# design.net
KiCad netlist of a schematic drawn in Altium Designer
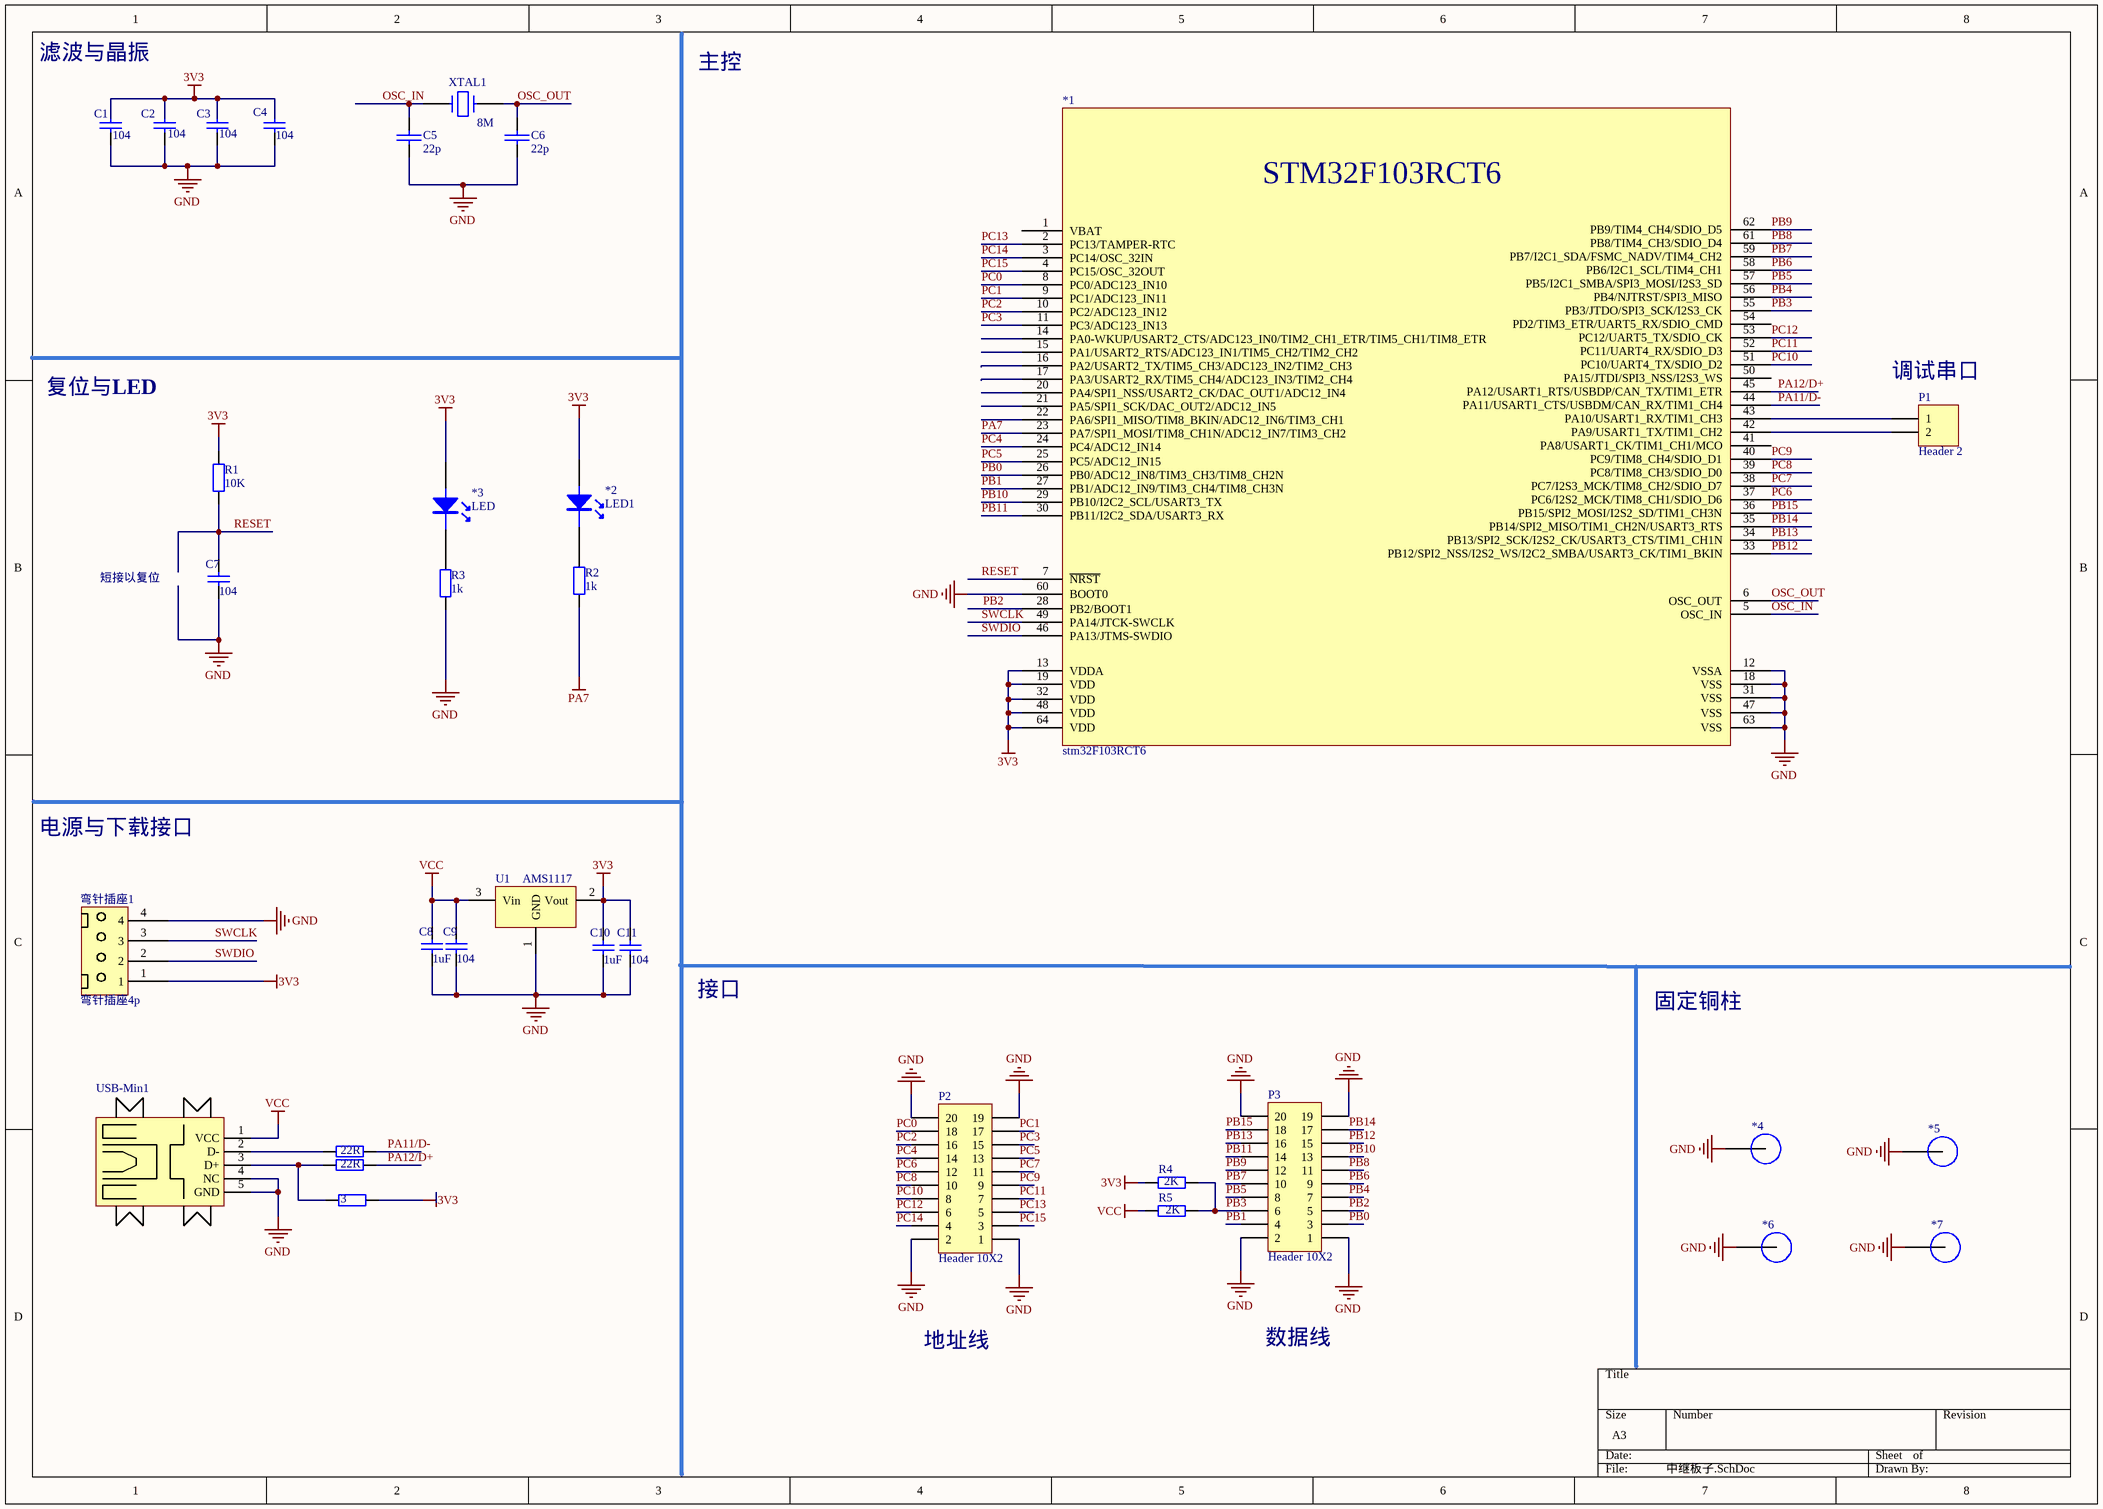
[diagram p0: 中继板子.SchDoc]

(export (version "E")
  (design (tool "Eeschema 10.0.6"))
  (components
    (comp (ref "*1")
      (value "stm32F103RCT6")
      (footprint "LQF64")
      (libsource (lib "Lee") (part "stm32F103RCT6"))
    )
    (comp (ref "*2") (value "LED1") (footprint "LED 0805B") (libsource (lib "Lee") (part "LED")))
    (comp (ref "*3") (value "LED") (footprint "LED 0805B") (libsource (lib "Lee") (part "LED")))
    (comp (ref "*4") (value "定位孔") (footprint "定位孔") (libsource (lib "Lee") (part "定位孔")))
    (comp (ref "*5") (value "定位孔") (footprint "定位孔") (libsource (lib "Lee") (part "定位孔")))
    (comp (ref "*6") (value "定位孔") (footprint "定位孔") (libsource (lib "Lee") (part "定位孔")))
    (comp (ref "*7") (value "定位孔") (footprint "定位孔") (libsource (lib "Lee") (part "定位孔")))
    (comp (ref "1") (value "22R") (footprint "R 0603") (libsource (lib "") (part "Res_1")))
    (comp (ref "2") (value "22R") (footprint "R 0603") (libsource (lib "") (part "Res_1")))
    (comp (ref "3") (value "Res") (footprint "R 0603") (libsource (lib "") (part "Res_2")))
    (comp (ref "C1") (value "104") (footprint "R 0603") (libsource (lib "Lee") (part "Cap")))
    (comp (ref "C2") (value "104") (footprint "R 0603") (libsource (lib "Lee") (part "Cap")))
    (comp (ref "C3") (value "104") (footprint "R 0603") (libsource (lib "Lee") (part "Cap")))
    (comp (ref "C4") (value "104") (footprint "R 0603") (libsource (lib "Lee") (part "Cap")))
    (comp (ref "C5") (value "22p") (footprint "R 0603") (libsource (lib "自创") (part "CAP")))
    (comp (ref "C6") (value "22p") (footprint "R 0603") (libsource (lib "自创") (part "CAP")))
    (comp (ref "C7")
      (value "104")
      (footprint "R 0603")
      (description "Capacitor")
      (fields (field (name "Comment") "Cap") (field (name "PUBLISHER") "Altium Limited"))
      (libsource (lib "Miscellaneous Devices") (part "Cap"))
    )
    (comp (ref "C8")
      (value "1uF")
      (footprint "R 0603")
      (description "Capacitor")
      (fields (field (name "Comment") "Cap") (field (name "PUBLISHER") "Altium Limited"))
      (libsource (lib "Miscellaneous Devices") (part "Cap"))
    )
    (comp (ref "C9")
      (value "104")
      (footprint "R 0603")
      (description "Capacitor")
      (fields (field (name "Comment") "Cap") (field (name "PUBLISHER") "Altium Limited"))
      (libsource (lib "Miscellaneous Devices") (part "Cap"))
    )
    (comp (ref "C10")
      (value "1uF")
      (footprint "R 0603")
      (description "Capacitor")
      (fields (field (name "Comment") "Cap") (field (name "PUBLISHER") "Altium Limited"))
      (libsource (lib "Miscellaneous Devices") (part "Cap"))
    )
    (comp (ref "C11")
      (value "104")
      (footprint "R 0603")
      (description "Capacitor")
      (fields (field (name "Comment") "Cap") (field (name "PUBLISHER") "Altium Limited"))
      (libsource (lib "Miscellaneous Devices") (part "Cap"))
    )
    (comp (ref "P1")
      (value "Header 2")
      (footprint "HDR-1x2")
      (description "Header, 2-Pin")
      (fields (field (name "PUBLISHER") "Altium Limited"))
      (libsource (lib "Miscellaneous Connectors") (part "Header 2"))
    )
    (comp (ref "P2")
      (value "Header 10X2")
      (footprint "HDR-10X2_H")
      (description "Header, 10-Pin, Dual row")
      (fields (field (name "PUBLISHER") "Altium Limited"))
      (libsource (lib "Miscellaneous Connectors") (part "Header 10X2"))
    )
    (comp (ref "P3")
      (value "Header 10X2")
      (footprint "HDR-10X2_H")
      (description "Header, 10-Pin, Dual row")
      (fields (field (name "PUBLISHER") "Altium Limited"))
      (libsource (lib "Miscellaneous Connectors") (part "Header 10X2"))
    )
    (comp (ref "R1")
      (value "10K")
      (footprint "R 0603")
      (description "Resistor")
      (fields (field (name "Comment") "Res2") (field (name "PUBLISHER") "Altium Limited"))
      (libsource (lib "") (part "Res2_1"))
    )
    (comp (ref "R2") (value "1k") (footprint "R 0603") (libsource (lib "Lee") (part "Res")))
    (comp (ref "R3") (value "1k") (footprint "R 0603") (libsource (lib "Lee") (part "Res")))
    (comp (ref "R4")
      (value "2K")
      (footprint "R 0603")
      (description "Resistor")
      (fields (field (name "Comment") "Res2") (field (name "PUBLISHER") "Altium Limited"))
      (libsource (lib "自创") (part "Res2"))
    )
    (comp (ref "R5")
      (value "2K")
      (footprint "R 0603")
      (description "Resistor")
      (fields (field (name "Comment") "Res2") (field (name "PUBLISHER") "Altium Limited"))
      (libsource (lib "自创") (part "Res2"))
    )
    (comp (ref "U1")
      (value "AMS1117")
      (footprint "AMS1117")
      (description "3.3V电压转换器AMS1117")
      (libsource (lib "自创") (part "AMS1117_1"))
    )
    (comp (ref "USB-Min1")
      (value "USB-Mini")
      (footprint "USB-A/S_A")
      (libsource (lib "Lee") (part "USB-Mini"))
    )
    (comp (ref "XTAL1") (value "8M") (footprint "XTAL-49S DIP") (libsource (lib "自创") (part "XTAL32")))
    (comp (ref "弯针插座1") (value "弯针插座4p") (footprint "XH2.54-4P") (libsource (lib "Lee") (part "弯针插座4p")))
  )
  (nets
    (net (code "1") (name "/OSC_IN") (class "Default")
      (node (ref "*1") (pin "5") (pinfunction "OSC_IN_5") (pintype "passive"))
      (node (ref "C5") (pin "1") (pinfunction "1_1") (pintype "passive"))
      (node (ref "XTAL1") (pin "2") (pinfunction "2_2") (pintype "passive"))
    )
    (net (code "2") (name "/OSC_OUT") (class "Default")
      (node (ref "*1") (pin "6") (pinfunction "OSC_OUT_6") (pintype "passive"))
      (node (ref "C6") (pin "1") (pinfunction "1_1") (pintype "passive"))
      (node (ref "XTAL1") (pin "1") (pinfunction "1_1") (pintype "passive"))
    )
    (net (code "3") (name "/PA11{slash}D-") (class "Default")
      (node (ref "*1") (pin "44") (pinfunction "PA11/USART1_CTS/USBDM/CAN_RX/TIM1_CH4_44") (pintype "passive"))
      (node (ref "1") (pin "2") (pinfunction "2_2") (pintype "passive"))
    )
    (net (code "4") (name "/PA12{slash}D+") (class "Default")
      (node (ref "*1") (pin "45") (pinfunction "PA12/USART1_RTS/USBDP/CAN_TX/TIM1_ETR_45") (pintype "passive"))
      (node (ref "2") (pin "2") (pinfunction "2_2") (pintype "passive"))
    )
    (net (code "5") (name "/PB0") (class "Default")
      (node (ref "*1") (pin "26") (pinfunction "PB0/ADC12_IN8/TIM3_CH3/TIM8_CH2N_26") (pintype "passive"))
      (node (ref "P3") (pin "3") (pinfunction "3_3") (pintype "passive"))
    )
    (net (code "6") (name "/PB1") (class "Default")
      (node (ref "*1") (pin "27") (pinfunction "PB1/ADC12_IN9/TIM3_CH4/TIM8_CH3N_27") (pintype "passive"))
      (node (ref "P3") (pin "4") (pinfunction "4_4") (pintype "passive"))
    )
    (net (code "7") (name "/PB2") (class "Default")
      (node (ref "*1") (pin "28") (pinfunction "PB2/BOOT1_28") (pintype "passive"))
      (node (ref "P3") (pin "5") (pinfunction "5_5") (pintype "passive"))
    )
    (net (code "8") (name "/PB3") (class "Default")
      (node (ref "*1") (pin "55") (pinfunction "PB3/JTDO/SPI3_SCK/I2S3_CK_55") (pintype "passive"))
      (node (ref "P3") (pin "6") (pinfunction "6_6") (pintype "passive"))
      (node (ref "R4") (pin "1") (pinfunction "1_1") (pintype "passive"))
      (node (ref "R5") (pin "1") (pinfunction "1_1") (pintype "passive"))
    )
    (net (code "9") (name "/PB4") (class "Default")
      (node (ref "*1") (pin "56") (pinfunction "PB4/NJTRST/SPI3_MISO_56") (pintype "passive"))
      (node (ref "P3") (pin "7") (pinfunction "7_7") (pintype "passive"))
    )
    (net (code "10") (name "/PB5") (class "Default")
      (node (ref "*1") (pin "57") (pinfunction "PB5/I2C1_SMBA/SPI3_MOSI/I2S3_SD_57") (pintype "passive"))
      (node (ref "P3") (pin "8") (pinfunction "8_8") (pintype "passive"))
    )
    (net (code "11") (name "/PB6") (class "Default")
      (node (ref "*1") (pin "58") (pinfunction "PB6/I2C1_SCL/TIM4_CH1_58") (pintype "passive"))
      (node (ref "P3") (pin "9") (pinfunction "9_9") (pintype "passive"))
    )
    (net (code "12") (name "/PB7") (class "Default")
      (node (ref "*1") (pin "59") (pinfunction "PB7/I2C1_SDA/FSMC_NADV/TIM4_CH2_59") (pintype "passive"))
      (node (ref "P3") (pin "10") (pinfunction "10_10") (pintype "passive"))
    )
    (net (code "13") (name "/PB8") (class "Default")
      (node (ref "*1") (pin "61") (pinfunction "PB8/TIM4_CH3/SDIO_D4_61") (pintype "passive"))
      (node (ref "P3") (pin "11") (pinfunction "11_11") (pintype "passive"))
    )
    (net (code "14") (name "/PB9") (class "Default")
      (node (ref "*1") (pin "62") (pinfunction "PB9/TIM4_CH4/SDIO_D5_62") (pintype "passive"))
      (node (ref "P3") (pin "12") (pinfunction "12_12") (pintype "passive"))
    )
    (net (code "15") (name "/PB10") (class "Default")
      (node (ref "*1") (pin "29") (pinfunction "PB10/I2C2_SCL/USART3_TX_29") (pintype "passive"))
      (node (ref "P3") (pin "13") (pinfunction "13_13") (pintype "passive"))
    )
    (net (code "16") (name "/PB11") (class "Default")
      (node (ref "*1") (pin "30") (pinfunction "PB11/I2C2_SDA/USART3_RX_30") (pintype "passive"))
      (node (ref "P3") (pin "14") (pinfunction "14_14") (pintype "passive"))
    )
    (net (code "17") (name "/PB12") (class "Default")
      (node (ref "*1") (pin "33") (pinfunction "PB12/SPI2_NSS/I2S2_WS/I2C2_SMBA/USART3_CK/TIM1_BKIN_33") (pintype "passive"))
      (node (ref "P3") (pin "15") (pinfunction "15_15") (pintype "passive"))
    )
    (net (code "18") (name "/PB13") (class "Default")
      (node (ref "*1") (pin "34") (pinfunction "PB13/SPI2_SCK/I2S2_CK/USART3_CTS/TIM1_CH1N_34") (pintype "passive"))
      (node (ref "P3") (pin "16") (pinfunction "16_16") (pintype "passive"))
    )
    (net (code "19") (name "/PB14") (class "Default")
      (node (ref "*1") (pin "35") (pinfunction "PB14/SPI2_MISO/TIM1_CH2N/USART3_RTS_35") (pintype "passive"))
      (node (ref "P3") (pin "17") (pinfunction "17_17") (pintype "passive"))
    )
    (net (code "20") (name "/PB15") (class "Default")
      (node (ref "*1") (pin "36") (pinfunction "PB15/SPI2_MOSI/I2S2_SD/TIM1_CH3N_36") (pintype "passive"))
      (node (ref "P3") (pin "18") (pinfunction "18_18") (pintype "passive"))
    )
    (net (code "21") (name "/PC0") (class "Default")
      (node (ref "*1") (pin "8") (pinfunction "PC0/ADC123_IN10_8") (pintype "passive"))
      (node (ref "P2") (pin "18") (pinfunction "18_18") (pintype "passive"))
    )
    (net (code "22") (name "/PC1") (class "Default")
      (node (ref "*1") (pin "9") (pinfunction "PC1/ADC123_IN11_9") (pintype "passive"))
      (node (ref "P2") (pin "17") (pinfunction "17_17") (pintype "passive"))
    )
    (net (code "23") (name "/PC2") (class "Default")
      (node (ref "*1") (pin "10") (pinfunction "PC2/ADC123_IN12_10") (pintype "passive"))
      (node (ref "P2") (pin "16") (pinfunction "16_16") (pintype "passive"))
    )
    (net (code "24") (name "/PC3") (class "Default")
      (node (ref "*1") (pin "11") (pinfunction "PC3/ADC123_IN13_11") (pintype "passive"))
      (node (ref "P2") (pin "15") (pinfunction "15_15") (pintype "passive"))
    )
    (net (code "25") (name "/PC4") (class "Default")
      (node (ref "*1") (pin "24") (pinfunction "PC4/ADC12_IN14_24") (pintype "passive"))
      (node (ref "P2") (pin "14") (pinfunction "14_14") (pintype "passive"))
    )
    (net (code "26") (name "/PC5") (class "Default")
      (node (ref "*1") (pin "25") (pinfunction "PC5/ADC12_IN15_25") (pintype "passive"))
      (node (ref "P2") (pin "13") (pinfunction "13_13") (pintype "passive"))
    )
    (net (code "27") (name "/PC6") (class "Default")
      (node (ref "*1") (pin "37") (pinfunction "PC6/I2S2_MCK/TIM8_CH1/SDIO_D6_37") (pintype "passive"))
      (node (ref "P2") (pin "12") (pinfunction "12_12") (pintype "passive"))
    )
    (net (code "28") (name "/PC7") (class "Default")
      (node (ref "*1") (pin "38") (pinfunction "PC7/I2S3_MCK/TIM8_CH2/SDIO_D7_38") (pintype "passive"))
      (node (ref "P2") (pin "11") (pinfunction "11_11") (pintype "passive"))
    )
    (net (code "29") (name "/PC8") (class "Default")
      (node (ref "*1") (pin "39") (pinfunction "PC8/TIM8_CH3/SDIO_D0_39") (pintype "passive"))
      (node (ref "P2") (pin "10") (pinfunction "10_10") (pintype "passive"))
    )
    (net (code "30") (name "/PC9") (class "Default")
      (node (ref "*1") (pin "40") (pinfunction "PC9/TIM8_CH4/SDIO_D1_40") (pintype "passive"))
      (node (ref "P2") (pin "9") (pinfunction "9_9") (pintype "passive"))
    )
    (net (code "31") (name "/PC10") (class "Default")
      (node (ref "*1") (pin "51") (pinfunction "PC10/UART4_TX/SDIO_D2_51") (pintype "passive"))
      (node (ref "P2") (pin "8") (pinfunction "8_8") (pintype "passive"))
    )
    (net (code "32") (name "/PC11") (class "Default")
      (node (ref "*1") (pin "52") (pinfunction "PC11/UART4_RX/SDIO_D3_52") (pintype "passive"))
      (node (ref "P2") (pin "7") (pinfunction "7_7") (pintype "passive"))
    )
    (net (code "33") (name "/PC12") (class "Default")
      (node (ref "*1") (pin "53") (pinfunction "PC12/UART5_TX/SDIO_CK_53") (pintype "passive"))
      (node (ref "P2") (pin "6") (pinfunction "6_6") (pintype "passive"))
    )
    (net (code "34") (name "/PC13") (class "Default")
      (node (ref "*1") (pin "2") (pinfunction "PC13/TAMPER-RTC_2") (pintype "passive"))
      (node (ref "P2") (pin "5") (pinfunction "5_5") (pintype "passive"))
    )
    (net (code "35") (name "/PC14") (class "Default")
      (node (ref "*1") (pin "3") (pinfunction "PC14/OSC_32IN_3") (pintype "passive"))
      (node (ref "P2") (pin "4") (pinfunction "4_4") (pintype "passive"))
    )
    (net (code "36") (name "/PC15") (class "Default")
      (node (ref "*1") (pin "4") (pinfunction "PC15/OSC_32OUT_4") (pintype "passive"))
      (node (ref "P2") (pin "3") (pinfunction "3_3") (pintype "passive"))
    )
    (net (code "37") (name "/RESET") (class "Default")
      (node (ref "*1") (pin "7") (pinfunction "~{NRST}_7") (pintype "passive"))
      (node (ref "C7") (pin "2") (pinfunction "2_2") (pintype "passive"))
      (node (ref "R1") (pin "2") (pinfunction "2_2") (pintype "passive"))
    )
    (net (code "38") (name "/SWCLK") (class "Default")
      (node (ref "*1") (pin "49") (pinfunction "PA14/JTCK-SWCLK_49") (pintype "passive"))
      (node (ref "弯针插座1") (pin "3") (pinfunction "3_3") (pintype "passive"))
    )
    (net (code "39") (name "/SWDIO") (class "Default")
      (node (ref "*1") (pin "46") (pinfunction "PA13/JTMS-SWDIO_46") (pintype "passive"))
      (node (ref "弯针插座1") (pin "2") (pinfunction "2_2") (pintype "passive"))
    )
    (net (code "40") (name "3V3") (class "Default")
      (node (ref "*1") (pin "13") (pinfunction "VDDA_13") (pintype "passive"))
      (node (ref "*1") (pin "19") (pinfunction "VDD_19") (pintype "passive"))
      (node (ref "*1") (pin "32") (pinfunction "VDD_32") (pintype "passive"))
      (node (ref "*1") (pin "48") (pinfunction "VDD_48") (pintype "passive"))
      (node (ref "*1") (pin "64") (pinfunction "VDD_64") (pintype "passive"))
      (node (ref "*2") (pin "1") (pinfunction "1_1") (pintype "passive"))
      (node (ref "*3") (pin "1") (pinfunction "1_1") (pintype "passive"))
      (node (ref "3") (pin "1") (pinfunction "1_1") (pintype "passive"))
      (node (ref "C1") (pin "2") (pinfunction "2_2") (pintype "passive"))
      (node (ref "C10") (pin "2") (pinfunction "2_2") (pintype "passive"))
      (node (ref "C11") (pin "2") (pinfunction "2_2") (pintype "passive"))
      (node (ref "C2") (pin "2") (pinfunction "2_2") (pintype "passive"))
      (node (ref "C3") (pin "2") (pinfunction "2_2") (pintype "passive"))
      (node (ref "C4") (pin "2") (pinfunction "2_2") (pintype "passive"))
      (node (ref "R1") (pin "1") (pinfunction "1_1") (pintype "passive"))
      (node (ref "R4") (pin "2") (pinfunction "2_2") (pintype "passive"))
      (node (ref "U1") (pin "2") (pinfunction "Vout_2") (pintype "passive"))
      (node (ref "弯针插座1") (pin "1") (pinfunction "1_1") (pintype "passive"))
    )
    (net (code "41") (name "GND") (class "Default")
      (node (ref "*1") (pin "12") (pinfunction "VSSA_12") (pintype "passive"))
      (node (ref "*1") (pin "18") (pinfunction "VSS_18") (pintype "passive"))
      (node (ref "*1") (pin "31") (pinfunction "VSS_31") (pintype "passive"))
      (node (ref "*1") (pin "47") (pinfunction "VSS_47") (pintype "passive"))
      (node (ref "*1") (pin "60") (pinfunction "BOOT0_60") (pintype "passive"))
      (node (ref "*1") (pin "63") (pinfunction "VSS_63") (pintype "passive"))
      (node (ref "*4") (pin "1") (pintype "passive"))
      (node (ref "*5") (pin "1") (pintype "passive"))
      (node (ref "*6") (pin "1") (pintype "passive"))
      (node (ref "*7") (pin "1") (pintype "passive"))
      (node (ref "C1") (pin "1") (pinfunction "1_1") (pintype "passive"))
      (node (ref "C10") (pin "1") (pinfunction "1_1") (pintype "passive"))
      (node (ref "C11") (pin "1") (pinfunction "1_1") (pintype "passive"))
      (node (ref "C2") (pin "1") (pinfunction "1_1") (pintype "passive"))
      (node (ref "C3") (pin "1") (pinfunction "1_1") (pintype "passive"))
      (node (ref "C4") (pin "1") (pinfunction "1_1") (pintype "passive"))
      (node (ref "C5") (pin "2") (pinfunction "2_2") (pintype "passive"))
      (node (ref "C6") (pin "2") (pinfunction "2_2") (pintype "passive"))
      (node (ref "C7") (pin "1") (pinfunction "1_1") (pintype "passive"))
      (node (ref "C8") (pin "1") (pinfunction "1_1") (pintype "passive"))
      (node (ref "C9") (pin "1") (pinfunction "1_1") (pintype "passive"))
      (node (ref "P2") (pin "1") (pinfunction "1_1") (pintype "passive"))
      (node (ref "P2") (pin "19") (pinfunction "19_19") (pintype "passive"))
      (node (ref "P2") (pin "2") (pinfunction "2_2") (pintype "passive"))
      (node (ref "P2") (pin "20") (pinfunction "20_20") (pintype "passive"))
      (node (ref "P3") (pin "1") (pinfunction "1_1") (pintype "passive"))
      (node (ref "P3") (pin "19") (pinfunction "19_19") (pintype "passive"))
      (node (ref "P3") (pin "2") (pinfunction "2_2") (pintype "passive"))
      (node (ref "P3") (pin "20") (pinfunction "20_20") (pintype "passive"))
      (node (ref "R3") (pin "2") (pinfunction "2_2") (pintype "passive"))
      (node (ref "U1") (pin "1") (pinfunction "GND_1") (pintype "passive"))
      (node (ref "USB-Min1") (pin "4") (pinfunction "NC_4") (pintype "passive"))
      (node (ref "USB-Min1") (pin "5") (pinfunction "GND_5") (pintype "passive"))
      (node (ref "弯针插座1") (pin "4") (pinfunction "4_4") (pintype "passive"))
    )
    (net (code "42") (name "Net-(*1-PA9{slash}USART1_TX{slash}TIM1_CH2)") (class "Default")
      (node (ref "*1") (pin "42") (pinfunction "PA9/USART1_TX/TIM1_CH2_42") (pintype "passive"))
      (node (ref "P1") (pin "2") (pinfunction "2_2") (pintype "passive"))
    )
    (net (code "43") (name "Net-(*1-PA10{slash}USART1_RX{slash}TIM1_CH3)") (class "Default")
      (node (ref "*1") (pin "43") (pinfunction "PA10/USART1_RX/TIM1_CH3_43") (pintype "passive"))
      (node (ref "P1") (pin "1") (pinfunction "1_1") (pintype "passive"))
    )
    (net (code "44") (name "Net-(*2-Pad2)") (class "Default")
      (node (ref "*2") (pin "2") (pinfunction "2_2") (pintype "passive"))
      (node (ref "R2") (pin "1") (pinfunction "1_1") (pintype "passive"))
    )
    (net (code "45") (name "Net-(*3-Pad2)") (class "Default")
      (node (ref "*3") (pin "2") (pinfunction "2_2") (pintype "passive"))
      (node (ref "R3") (pin "1") (pinfunction "1_1") (pintype "passive"))
    )
    (net (code "46") (name "Net-(USB-Min1-D+)") (class "Default")
      (node (ref "2") (pin "1") (pinfunction "1_1") (pintype "passive"))
      (node (ref "3") (pin "2") (pinfunction "2_2") (pintype "passive"))
      (node (ref "USB-Min1") (pin "3") (pinfunction "D+_3") (pintype "passive"))
    )
    (net (code "47") (name "Net-(USB-Min1-D-)") (class "Default")
      (node (ref "1") (pin "1") (pinfunction "1_1") (pintype "passive"))
      (node (ref "USB-Min1") (pin "2") (pinfunction "D-_2") (pintype "passive"))
    )
    (net (code "48") (name "PA7") (class "Default")
      (node (ref "*1") (pin "23") (pinfunction "PA7/SPI1_MOSI/TIM8_CH1N/ADC12_IN7/TIM3_CH2_23") (pintype "passive"))
      (node (ref "R2") (pin "2") (pinfunction "2_2") (pintype "passive"))
    )
    (net (code "49") (name "VCC") (class "Default")
      (node (ref "C8") (pin "2") (pinfunction "2_2") (pintype "passive"))
      (node (ref "C9") (pin "2") (pinfunction "2_2") (pintype "passive"))
      (node (ref "R5") (pin "2") (pinfunction "2_2") (pintype "passive"))
      (node (ref "U1") (pin "3") (pinfunction "Vin_3") (pintype "passive"))
      (node (ref "USB-Min1") (pin "1") (pinfunction "VCC_1") (pintype "passive"))
    )
    (net (code "50") (name "unconnected-(*1-PA0-WKUP{slash}USART2_CTS{slash}ADC123_IN0{slash}TIM2_CH1_ETR{slash}TIM5_CH1{slash}TIM8_ETR-Pad14)") (class "Default")
      (node (ref "*1") (pin "14") (pinfunction "PA0-WKUP/USART2_CTS/ADC123_IN0/TIM2_CH1_ETR/TIM5_CH1/TIM8_ETR_14") (pintype "passive"))
    )
    (net (code "51") (name "unconnected-(*1-PA1{slash}USART2_RTS{slash}ADC123_IN1{slash}TIM5_CH2{slash}TIM2_CH2-Pad15)") (class "Default")
      (node (ref "*1") (pin "15") (pinfunction "PA1/USART2_RTS/ADC123_IN1/TIM5_CH2/TIM2_CH2_15") (pintype "passive"))
    )
    (net (code "52") (name "unconnected-(*1-PA2{slash}USART2_TX{slash}TIM5_CH3{slash}ADC123_IN2{slash}TIM2_CH3-Pad16)") (class "Default")
      (node (ref "*1") (pin "16") (pinfunction "PA2/USART2_TX/TIM5_CH3/ADC123_IN2/TIM2_CH3_16") (pintype "passive"))
    )
    (net (code "53") (name "unconnected-(*1-PA3{slash}USART2_RX{slash}TIM5_CH4{slash}ADC123_IN3{slash}TIM2_CH4-Pad17)") (class "Default")
      (node (ref "*1") (pin "17") (pinfunction "PA3/USART2_RX/TIM5_CH4/ADC123_IN3/TIM2_CH4_17") (pintype "passive"))
    )
    (net (code "54") (name "unconnected-(*1-PA4{slash}SPI1_NSS{slash}USART2_CK{slash}DAC_OUT1{slash}ADC12_IN4-Pad20)") (class "Default")
      (node (ref "*1") (pin "20") (pinfunction "PA4/SPI1_NSS/USART2_CK/DAC_OUT1/ADC12_IN4_20") (pintype "passive"))
    )
    (net (code "55") (name "unconnected-(*1-PA5{slash}SPI1_SCK{slash}DAC_OUT2{slash}ADC12_IN5-Pad21)") (class "Default")
      (node (ref "*1") (pin "21") (pinfunction "PA5/SPI1_SCK/DAC_OUT2/ADC12_IN5_21") (pintype "passive"))
    )
    (net (code "56") (name "unconnected-(*1-PA6{slash}SPI1_MISO{slash}TIM8_BKIN{slash}ADC12_IN6{slash}TIM3_CH1-Pad22)") (class "Default")
      (node (ref "*1") (pin "22") (pinfunction "PA6/SPI1_MISO/TIM8_BKIN/ADC12_IN6/TIM3_CH1_22") (pintype "passive"))
    )
    (net (code "57") (name "unconnected-(*1-PA8{slash}USART1_CK{slash}TIM1_CH1{slash}MCO-Pad41)") (class "Default")
      (node (ref "*1") (pin "41") (pinfunction "PA8/USART1_CK/TIM1_CH1/MCO_41") (pintype "passive"))
    )
    (net (code "58") (name "unconnected-(*1-PA15{slash}JTDI{slash}SPI3_NSS{slash}I2S3_WS-Pad50)") (class "Default")
      (node (ref "*1") (pin "50") (pinfunction "PA15/JTDI/SPI3_NSS/I2S3_WS_50") (pintype "passive"))
    )
    (net (code "59") (name "unconnected-(*1-PD2{slash}TIM3_ETR{slash}UART5_RX{slash}SDIO_CMD-Pad54)") (class "Default")
      (node (ref "*1") (pin "54") (pinfunction "PD2/TIM3_ETR/UART5_RX/SDIO_CMD_54") (pintype "passive"))
    )
    (net (code "60") (name "unconnected-(*1-VBAT-Pad1)") (class "Default")
      (node (ref "*1") (pin "1") (pinfunction "VBAT_1") (pintype "passive"))
    )
  )
)
